# CAN.net
KiCad netlist of a schematic drawn in Altium Designer
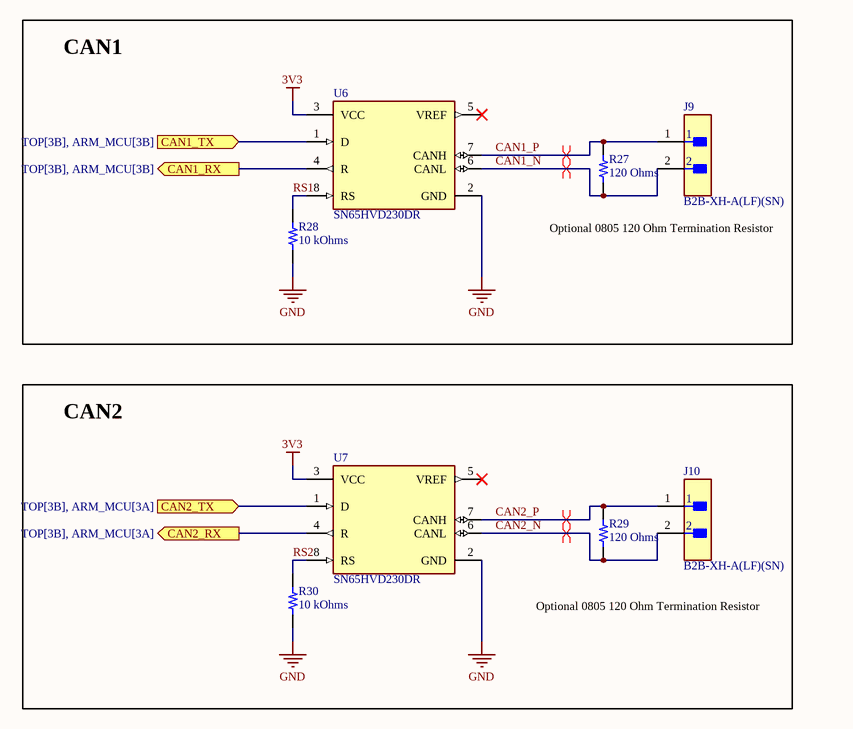
[diagram p0: CAN.SchDoc]

(export (version "E")
  (design (tool "Eeschema 10.0.6"))
  (components
    (comp (ref "J9")
      (value "B2B-XH-A(LF)(SN)")
      (footprint "FP-B2B-XH-A_LF_SN-MFG")
      (description "CONN HEADER VERT 2POS 2.5MM")
      (libsource (lib "Altium Content Vault") (part "3bc925449376181038e59eaffc5286c"))
    )
    (comp (ref "J10")
      (value "B2B-XH-A(LF)(SN)")
      (footprint "FP-B2B-XH-A_LF_SN-MFG")
      (description "CONN HEADER VERT 2POS 2.5MM")
      (libsource (lib "Altium Content Vault") (part "3bc925449376181038e59eaffc5286c"))
    )
    (comp (ref "R27")
      (value "120 Ohms")
      (footprint "RES 0603_1608")
      (description "RES 120 OHM 0.05% 1/10W 0603")
      (fields (field (name "PART NUMBER") "TNPU0603120RAYEN00") (field (name "MANUFACTURER") "Vishay Dale"))
      (libsource (lib "Celestial Altium Library - altium_library") (part "Resistor"))
    )
    (comp (ref "R28")
      (value "10 kOhms")
      (footprint "RES 0603_1608")
      (description "P2TC0603 2PPM/C 10K 0,01% N TA")
      (fields
        (field (name "PART NUMBER") "P2TC0603D1002LNTA")
        (field (name "MANUFACTURER") "Vishay Sfernice")
      )
      (libsource (lib "Celestial Altium Library - altium_library") (part "Resistor"))
    )
    (comp (ref "R29")
      (value "120 Ohms")
      (footprint "RES 0603_1608")
      (description "RES 120 OHM 0.05% 1/10W 0603")
      (fields (field (name "PART NUMBER") "TNPU0603120RAYEN00") (field (name "MANUFACTURER") "Vishay Dale"))
      (libsource (lib "Celestial Altium Library - altium_library") (part "Resistor"))
    )
    (comp (ref "R30")
      (value "10 kOhms")
      (footprint "RES 0603_1608")
      (description "P2TC0603 2PPM/C 10K 0,01% N TA")
      (fields
        (field (name "PART NUMBER") "P2TC0603D1002LNTA")
        (field (name "MANUFACTURER") "Vishay Sfernice")
      )
      (libsource (lib "Celestial Altium Library - altium_library") (part "Resistor"))
    )
    (comp (ref "U6")
      (value "SN65HVD230DR")
      (footprint "FP-D0008A-IPC_A")
      (description "IC TRANSCEIVER HALF 1/1 8SOIC")
      (libsource (lib "Altium Content Vault") (part "43b56812b1adf0e60a7acfb7c27ab91"))
    )
    (comp (ref "U7")
      (value "SN65HVD230DR")
      (footprint "FP-D0008A-IPC_A")
      (description "IC TRANSCEIVER HALF 1/1 8SOIC")
      (libsource (lib "Altium Content Vault") (part "43b56812b1adf0e60a7acfb7c27ab91"))
    )
  )
  (nets
    (net (code "1") (name "/CAN1_N") (class "Default")
      (node (ref "J9") (pin "2") (pinfunction "2_2") (pintype "passive"))
      (node (ref "R27") (pin "1") (pinfunction "1_1") (pintype "passive"))
      (node (ref "U6") (pin "6") (pinfunction "CANL_6") (pintype "bidirectional"))
    )
    (net (code "2") (name "/CAN1_P") (class "Default")
      (node (ref "J9") (pin "1") (pinfunction "1_1") (pintype "passive"))
      (node (ref "R27") (pin "2") (pinfunction "2_2") (pintype "passive"))
      (node (ref "U6") (pin "7") (pinfunction "CANH_7") (pintype "bidirectional"))
    )
    (net (code "3") (name "/CAN1_RX") (class "Default")
      (node (ref "U6") (pin "4") (pinfunction "R_4") (pintype "output"))
    )
    (net (code "4") (name "/CAN1_TX") (class "Default")
      (node (ref "U6") (pin "1") (pinfunction "D_1") (pintype "input"))
    )
    (net (code "5") (name "/CAN2_N") (class "Default")
      (node (ref "J10") (pin "2") (pinfunction "2_2") (pintype "passive"))
      (node (ref "R29") (pin "1") (pinfunction "1_1") (pintype "passive"))
      (node (ref "U7") (pin "6") (pinfunction "CANL_6") (pintype "bidirectional"))
    )
    (net (code "6") (name "/CAN2_P") (class "Default")
      (node (ref "J10") (pin "1") (pinfunction "1_1") (pintype "passive"))
      (node (ref "R29") (pin "2") (pinfunction "2_2") (pintype "passive"))
      (node (ref "U7") (pin "7") (pinfunction "CANH_7") (pintype "bidirectional"))
    )
    (net (code "7") (name "/CAN2_RX") (class "Default")
      (node (ref "U7") (pin "4") (pinfunction "R_4") (pintype "output"))
    )
    (net (code "8") (name "/CAN2_TX") (class "Default")
      (node (ref "U7") (pin "1") (pinfunction "D_1") (pintype "input"))
    )
    (net (code "9") (name "/RS1") (class "Default")
      (node (ref "R28") (pin "2") (pinfunction "2_2") (pintype "passive"))
      (node (ref "U6") (pin "8") (pinfunction "RS_8") (pintype "input"))
    )
    (net (code "10") (name "/RS2") (class "Default")
      (node (ref "R30") (pin "2") (pinfunction "2_2") (pintype "passive"))
      (node (ref "U7") (pin "8") (pinfunction "RS_8") (pintype "input"))
    )
    (net (code "11") (name "3V3") (class "Default")
      (node (ref "U6") (pin "3") (pinfunction "VCC_3") (pintype "power_in"))
      (node (ref "U7") (pin "3") (pinfunction "VCC_3") (pintype "power_in"))
    )
    (net (code "12") (name "GND") (class "Default")
      (node (ref "R28") (pin "1") (pinfunction "1_1") (pintype "passive"))
      (node (ref "R30") (pin "1") (pinfunction "1_1") (pintype "passive"))
      (node (ref "U6") (pin "2") (pinfunction "GND_2") (pintype "power_in"))
      (node (ref "U7") (pin "2") (pinfunction "GND_2") (pintype "power_in"))
    )
    (net (code "13") (name "unconnected-(U6-VREF-Pad5)") (class "Default")
      (node (ref "U6") (pin "5") (pinfunction "VREF_5") (pintype "output+no_connect"))
    )
    (net (code "14") (name "unconnected-(U7-VREF-Pad5)") (class "Default")
      (node (ref "U7") (pin "5") (pinfunction "VREF_5") (pintype "output+no_connect"))
    )
  )
)
